# main1.net
KiCad netlist of a schematic drawn in EAGLE
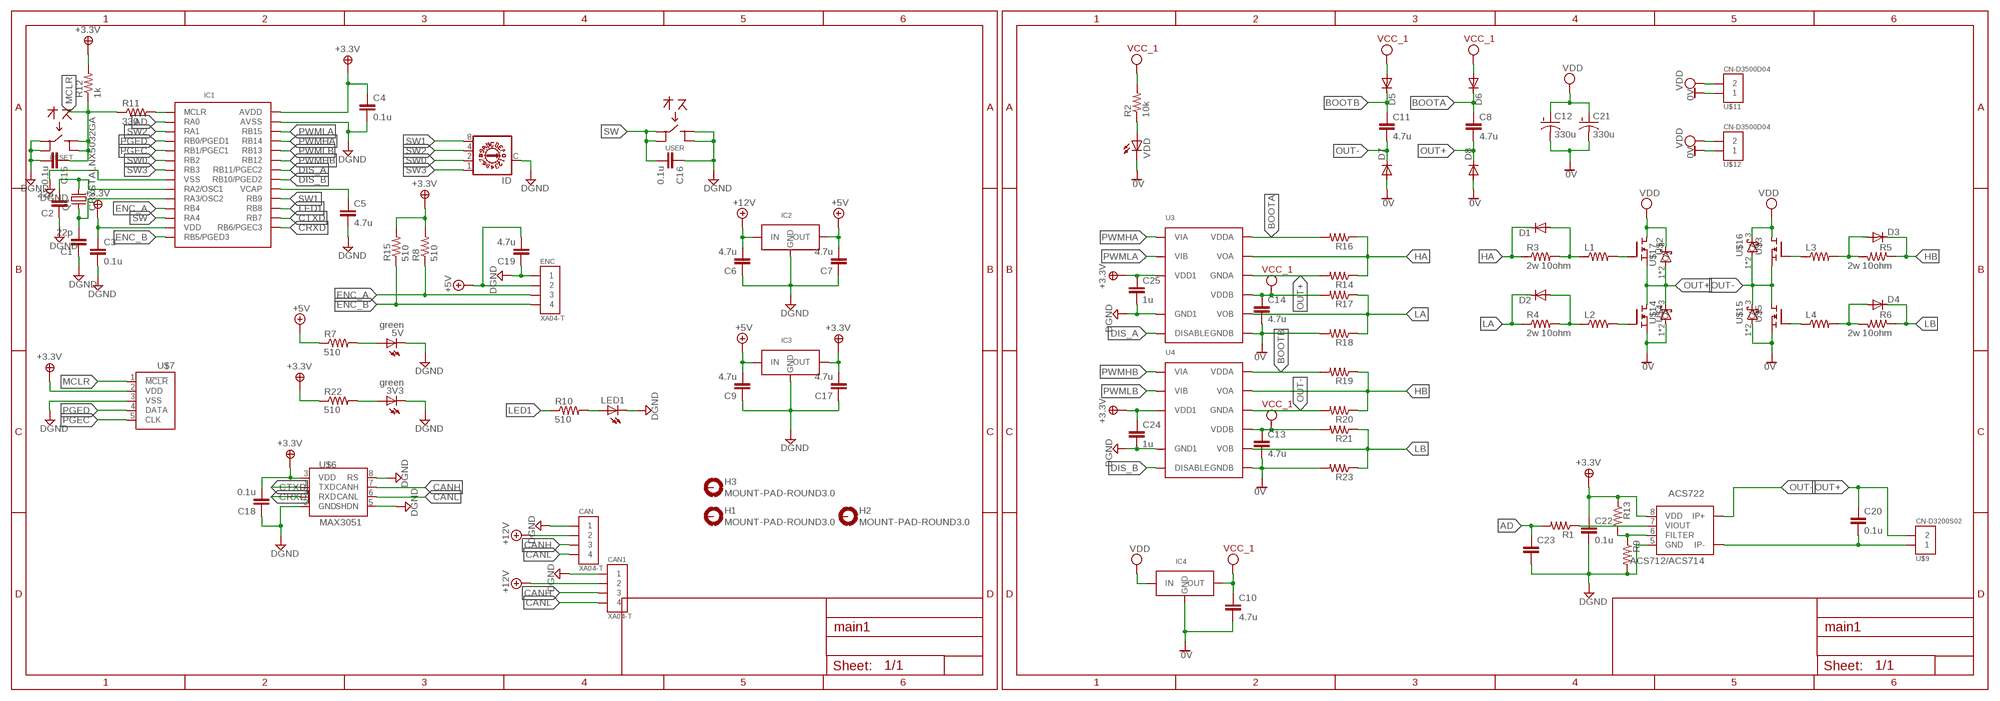
[diagram p0: schematic, sheet 1]

(export (version "E")
  (design (tool "Eeschema 10.0.6"))
  (components
    (comp (ref "3V3")
      (value "green")
      (footprint "eagle-import:CHIPLED_0603")
      (libsource (lib "eagle-import") (part "LEDCHIPLED_0603"))
    )
    (comp (ref "5V")
      (value "green")
      (footprint "eagle-import:CHIPLED_0603")
      (libsource (lib "eagle-import") (part "LEDCHIPLED_0603"))
    )
    (comp (ref "ACS722")
      (value "ACS712/ACS714")
      (footprint "eagle-import:SOIC8")
      (libsource (lib "eagle-import") (part "ACS712/ACS714"))
    )
    (comp (ref "C1")
      (value "22p")
      (footprint "eagle-import:C0603K")
      (libsource (lib "eagle-import") (part "C-EUC0603K"))
    )
    (comp (ref "C2")
      (value "22p")
      (footprint "eagle-import:C0603K")
      (libsource (lib "eagle-import") (part "C-EUC0603K"))
    )
    (comp (ref "C3")
      (value "0.1u")
      (footprint "eagle-import:C0603K")
      (libsource (lib "eagle-import") (part "C-EUC0603K"))
    )
    (comp (ref "C4")
      (value "0.1u")
      (footprint "eagle-import:C0603K")
      (libsource (lib "eagle-import") (part "C-EUC0603K"))
    )
    (comp (ref "C5")
      (value "4.7u")
      (footprint "eagle-import:C0805K")
      (libsource (lib "eagle-import") (part "C-EUC0805K"))
    )
    (comp (ref "C6")
      (value "4.7u")
      (footprint "eagle-import:C0805K")
      (libsource (lib "eagle-import") (part "C-EUC0805K"))
    )
    (comp (ref "C7")
      (value "4.7u")
      (footprint "eagle-import:C0805K")
      (libsource (lib "eagle-import") (part "C-EUC0805K"))
    )
    (comp (ref "C8")
      (value "4.7u")
      (footprint "eagle-import:C0805K")
      (libsource (lib "eagle-import") (part "C-EUC0805K"))
    )
    (comp (ref "C9")
      (value "4.7u")
      (footprint "eagle-import:C0805K")
      (libsource (lib "eagle-import") (part "C-EUC0805K"))
    )
    (comp (ref "C10")
      (value "4.7u")
      (footprint "eagle-import:C0805K")
      (libsource (lib "eagle-import") (part "C-EUC0805K"))
    )
    (comp (ref "C11")
      (value "4.7u")
      (footprint "eagle-import:C0805K")
      (libsource (lib "eagle-import") (part "C-EUC0805K"))
    )
    (comp (ref "C12")
      (value "330u")
      (footprint "eagle-import:PANASONIC_G")
      (libsource (lib "eagle-import") (part "CPOL-USG"))
    )
    (comp (ref "C13")
      (value "4.7u")
      (footprint "eagle-import:C0805K")
      (libsource (lib "eagle-import") (part "C-EUC0805K"))
    )
    (comp (ref "C14")
      (value "4.7u")
      (footprint "eagle-import:C0805K")
      (libsource (lib "eagle-import") (part "C-EUC0805K"))
    )
    (comp (ref "C15")
      (value "0.1u")
      (footprint "eagle-import:C0603K")
      (libsource (lib "eagle-import") (part "C-EUC0603K"))
    )
    (comp (ref "C16")
      (value "0.1u")
      (footprint "eagle-import:C0603K")
      (libsource (lib "eagle-import") (part "C-EUC0603K"))
    )
    (comp (ref "C17")
      (value "4.7u")
      (footprint "eagle-import:C0805K")
      (libsource (lib "eagle-import") (part "C-EUC0805K"))
    )
    (comp (ref "C18")
      (value "0.1u")
      (footprint "eagle-import:C0603K")
      (libsource (lib "eagle-import") (part "C-EUC0603K"))
    )
    (comp (ref "C19")
      (value "4.7u")
      (footprint "eagle-import:C0805K")
      (libsource (lib "eagle-import") (part "C-EUC0805K"))
    )
    (comp (ref "C20")
      (value "0.1u")
      (footprint "eagle-import:C0603K")
      (libsource (lib "eagle-import") (part "C-EUC0603K"))
    )
    (comp (ref "C21")
      (value "330u")
      (footprint "eagle-import:PANASONIC_G")
      (libsource (lib "eagle-import") (part "CPOL-USG"))
    )
    (comp (ref "C22")
      (value "0.1u")
      (footprint "eagle-import:C1206")
      (libsource (lib "eagle-import") (part "C-EUC1206"))
    )
    (comp (ref "C23")
      (value "C-EUC0603K")
      (footprint "eagle-import:C0603K")
      (libsource (lib "eagle-import") (part "C-EUC0603K"))
    )
    (comp (ref "C24")
      (value "1u")
      (footprint "eagle-import:C0603K")
      (libsource (lib "eagle-import") (part "C-EUC0603K"))
    )
    (comp (ref "C25")
      (value "1u")
      (footprint "eagle-import:C0603K")
      (libsource (lib "eagle-import") (part "C-EUC0603K"))
    )
    (comp (ref "CAN")
      (value "XA04-T")
      (footprint "eagle-import:XA04")
      (libsource (lib "eagle-import") (part "XA04-T"))
    )
    (comp (ref "CAN1")
      (value "XA04-T")
      (footprint "eagle-import:XA04")
      (libsource (lib "eagle-import") (part "XA04-T"))
    )
    (comp (ref "D1")
      (value "DIODE-SOD123")
      (footprint "eagle-import:SOD123")
      (libsource (lib "eagle-import") (part "DIODE-SOD123"))
    )
    (comp (ref "D2")
      (value "DIODE-SOD123")
      (footprint "eagle-import:SOD123")
      (libsource (lib "eagle-import") (part "DIODE-SOD123"))
    )
    (comp (ref "D3")
      (value "DIODE-SOD123")
      (footprint "eagle-import:SOD123")
      (libsource (lib "eagle-import") (part "DIODE-SOD123"))
    )
    (comp (ref "D4")
      (value "DIODE-SOD123")
      (footprint "eagle-import:SOD123")
      (libsource (lib "eagle-import") (part "DIODE-SOD123"))
    )
    (comp (ref "D5")
      (value "DIODE-SOD123")
      (footprint "eagle-import:SOD123")
      (libsource (lib "eagle-import") (part "DIODE-SOD123"))
    )
    (comp (ref "D6")
      (value "DIODE-SOD123")
      (footprint "eagle-import:SOD123")
      (libsource (lib "eagle-import") (part "DIODE-SOD123"))
    )
    (comp (ref "D7")
      (value "DIODE-SOD123")
      (footprint "eagle-import:SOD123")
      (libsource (lib "eagle-import") (part "DIODE-SOD123"))
    )
    (comp (ref "D8")
      (value "DIODE-SOD123")
      (footprint "eagle-import:SOD123")
      (libsource (lib "eagle-import") (part "DIODE-SOD123"))
    )
    (comp (ref "ENC")
      (value "XA04-T")
      (footprint "eagle-import:XA04")
      (libsource (lib "eagle-import") (part "XA04-T"))
    )
    (comp (ref "H1")
      (value "MOUNT-PAD-ROUND3.0")
      (footprint "eagle-import:3,0-PAD")
      (libsource (lib "eagle-import") (part "MOUNT-PAD-ROUND3.0"))
    )
    (comp (ref "H2")
      (value "MOUNT-PAD-ROUND3.0")
      (footprint "eagle-import:3,0-PAD")
      (libsource (lib "eagle-import") (part "MOUNT-PAD-ROUND3.0"))
    )
    (comp (ref "H3")
      (value "MOUNT-PAD-ROUND3.0")
      (footprint "eagle-import:3,0-PAD")
      (libsource (lib "eagle-import") (part "MOUNT-PAD-ROUND3.0"))
    )
    (comp (ref "IC1")
      (value "DSPIC33FJ128MC802")
      (footprint "eagle-import:SOIC28")
      (libsource (lib "eagle-import") (part "DSPIC33FJ128MC802"))
    )
    (comp (ref "IC2")
      (value "REGULATER_MIC39100-5.0WS")
      (footprint "eagle-import:SOT-223")
      (libsource (lib "eagle-import") (part "REGULATER_MIC39100-3.3WS"))
    )
    (comp (ref "IC3")
      (value "REGULATER_AZ1117CR")
      (footprint "eagle-import:SOT89")
      (libsource (lib "eagle-import") (part "REGULATER_AZ1117CR"))
    )
    (comp (ref "IC4")
      (value "REGULATER_MIC2940A-5.0WU")
      (footprint "eagle-import:TO-263-3")
      (libsource (lib "eagle-import") (part "REGULATER_MIC2940A-5.0WU"))
    )
    (comp (ref "ID")
      (value "A1353HEX")
      (footprint "eagle-import:A1353HEX")
      (libsource (lib "eagle-import") (part "A1353HEX"))
    )
    (comp (ref "L1")
      (value "R-US_R0805")
      (footprint "eagle-import:R0805")
      (libsource (lib "eagle-import") (part "R-US_R0805"))
    )
    (comp (ref "L2")
      (value "R-US_R0805")
      (footprint "eagle-import:R0805")
      (libsource (lib "eagle-import") (part "R-US_R0805"))
    )
    (comp (ref "L3")
      (value "R-US_R0805")
      (footprint "eagle-import:R0805")
      (libsource (lib "eagle-import") (part "R-US_R0805"))
    )
    (comp (ref "L4")
      (value "R-US_R0805")
      (footprint "eagle-import:R0805")
      (libsource (lib "eagle-import") (part "R-US_R0805"))
    )
    (comp (ref "LED1")
      (value "LEDCHIPLED_0603")
      (footprint "eagle-import:CHIPLED_0603")
      (libsource (lib "eagle-import") (part "LEDCHIPLED_0603"))
    )
    (comp (ref "Q1")
      (value "CRYSTALNX5032GA")
      (footprint "eagle-import:NX5032GA")
      (libsource (lib "eagle-import") (part "CRYSTALNX5032GA"))
    )
    (comp (ref "R1")
      (value "R-US_R0603")
      (footprint "eagle-import:R0603")
      (libsource (lib "eagle-import") (part "R-US_R0603"))
    )
    (comp (ref "R2")
      (value "10k")
      (footprint "eagle-import:R0603")
      (libsource (lib "eagle-import") (part "R-US_R0603"))
    )
    (comp (ref "R3")
      (value "2w 10ohm")
      (footprint "eagle-import:R2512")
      (libsource (lib "eagle-import") (part "R-US_R2512"))
    )
    (comp (ref "R4")
      (value "2w 10ohm")
      (footprint "eagle-import:R2512")
      (libsource (lib "eagle-import") (part "R-US_R2512"))
    )
    (comp (ref "R5")
      (value "2w 10ohm")
      (footprint "eagle-import:R2512")
      (libsource (lib "eagle-import") (part "R-US_R2512"))
    )
    (comp (ref "R6")
      (value "2w 10ohm")
      (footprint "eagle-import:R2512")
      (libsource (lib "eagle-import") (part "R-US_R2512"))
    )
    (comp (ref "R7")
      (value "510")
      (footprint "eagle-import:R0603")
      (libsource (lib "eagle-import") (part "R-US_R0603"))
    )
    (comp (ref "R8")
      (value "510")
      (footprint "eagle-import:R0603")
      (libsource (lib "eagle-import") (part "R-US_R0603"))
    )
    (comp (ref "R9")
      (value "R-US_R0603")
      (footprint "eagle-import:R0603")
      (libsource (lib "eagle-import") (part "R-US_R0603"))
    )
    (comp (ref "R10")
      (value "510")
      (footprint "eagle-import:R0603")
      (libsource (lib "eagle-import") (part "R-US_R0603"))
    )
    (comp (ref "R11")
      (value "330")
      (footprint "eagle-import:R0603")
      (libsource (lib "eagle-import") (part "R-US_R0603"))
    )
    (comp (ref "R12")
      (value "1k")
      (footprint "eagle-import:R0603")
      (libsource (lib "eagle-import") (part "R-US_R0603"))
    )
    (comp (ref "R13")
      (value "R-US_R0603")
      (footprint "eagle-import:R0603")
      (libsource (lib "eagle-import") (part "R-US_R0603"))
    )
    (comp (ref "R14")
      (value "R-US_R0603")
      (footprint "eagle-import:R0603")
      (libsource (lib "eagle-import") (part "R-US_R0603"))
    )
    (comp (ref "R15")
      (value "510")
      (footprint "eagle-import:R0603")
      (libsource (lib "eagle-import") (part "R-US_R0603"))
    )
    (comp (ref "R16")
      (value "R-US_R0603")
      (footprint "eagle-import:R0603")
      (libsource (lib "eagle-import") (part "R-US_R0603"))
    )
    (comp (ref "R17")
      (value "R-US_R0603")
      (footprint "eagle-import:R0603")
      (libsource (lib "eagle-import") (part "R-US_R0603"))
    )
    (comp (ref "R18")
      (value "R-US_R0603")
      (footprint "eagle-import:R0603")
      (libsource (lib "eagle-import") (part "R-US_R0603"))
    )
    (comp (ref "R19")
      (value "R-US_R0603")
      (footprint "eagle-import:R0603")
      (libsource (lib "eagle-import") (part "R-US_R0603"))
    )
    (comp (ref "R20")
      (value "R-US_R0603")
      (footprint "eagle-import:R0603")
      (libsource (lib "eagle-import") (part "R-US_R0603"))
    )
    (comp (ref "R21")
      (value "R-US_R0603")
      (footprint "eagle-import:R0603")
      (libsource (lib "eagle-import") (part "R-US_R0603"))
    )
    (comp (ref "R22")
      (value "510")
      (footprint "eagle-import:R0603")
      (libsource (lib "eagle-import") (part "R-US_R0603"))
    )
    (comp (ref "R23")
      (value "R-US_R0603")
      (footprint "eagle-import:R0603")
      (libsource (lib "eagle-import") (part "R-US_R0603"))
    )
    (comp (ref "RESET")
      (value "SWITCH_4PALPS")
      (footprint "eagle-import:SKRP")
      (libsource (lib "eagle-import") (part "SWITCH_4PALPS"))
    )
    (comp (ref "U$1")
      (value "CN-D3500D04")
      (footprint "eagle-import:D-3500D04")
      (libsource (lib "eagle-import") (part "CN-D3500D04"))
    )
    (comp (ref "U$2")
      (value "FET_NCH_FDMS86152")
      (footprint "eagle-import:PQFN_8L")
      (libsource (lib "eagle-import") (part "FET_NCH_FDMS86152"))
    )
    (comp (ref "U$3")
      (value "FET_NCH_FDMS86152")
      (footprint "eagle-import:PQFN_8L")
      (libsource (lib "eagle-import") (part "FET_NCH_FDMS86152"))
    )
    (comp (ref "U$4")
      (value "FET_NCH_FDMS86152")
      (footprint "eagle-import:PQFN_8L")
      (libsource (lib "eagle-import") (part "FET_NCH_FDMS86152"))
    )
    (comp (ref "U$5")
      (value "FET_NCH_FDMS86152")
      (footprint "eagle-import:PQFN_8L")
      (libsource (lib "eagle-import") (part "FET_NCH_FDMS86152"))
    )
    (comp (ref "U$6")
      (value "MAX3051")
      (footprint "eagle-import:SOIC8")
      (libsource (lib "eagle-import") (part "MAX3051"))
    )
    (comp (ref "U$7")
      (value "WRITE_FOR_PICT")
      (footprint "eagle-import:ZH05")
      (libsource (lib "eagle-import") (part "WRITE_FOR_PICT"))
    )
    (comp (ref "U$9")
      (value "CN-D3200S02")
      (footprint "eagle-import:D-3200S02-S")
      (libsource (lib "eagle-import") (part "CN-D3200S02"))
    )
    (comp (ref "U$14")
      (value "SCHOTTKY_BARRIER_DIODE_FSV560")
      (footprint "eagle-import:TO-277")
      (libsource (lib "eagle-import") (part "SCHOTTKY_BARRIER_DIODE_FSV560"))
    )
    (comp (ref "U$15")
      (value "SCHOTTKY_BARRIER_DIODE_FSV560")
      (footprint "eagle-import:TO-277")
      (libsource (lib "eagle-import") (part "SCHOTTKY_BARRIER_DIODE_FSV560"))
    )
    (comp (ref "U$16")
      (value "SCHOTTKY_BARRIER_DIODE_FSV560")
      (footprint "eagle-import:TO-277")
      (libsource (lib "eagle-import") (part "SCHOTTKY_BARRIER_DIODE_FSV560"))
    )
    (comp (ref "U$17")
      (value "SCHOTTKY_BARRIER_DIODE_FSV560")
      (footprint "eagle-import:TO-277")
      (libsource (lib "eagle-import") (part "SCHOTTKY_BARRIER_DIODE_FSV560"))
    )
    (comp (ref "U3")
      (value "ADUM3223_SMD")
      (footprint "eagle-import:SOIC16_N")
      (libsource (lib "eagle-import") (part "ADUM3223_SMD"))
    )
    (comp (ref "U4")
      (value "ADUM3223_SMD")
      (footprint "eagle-import:SOIC16_N")
      (libsource (lib "eagle-import") (part "ADUM3223_SMD"))
    )
    (comp (ref "USER")
      (value "SWITCH_4PALPS")
      (footprint "eagle-import:SKRP")
      (libsource (lib "eagle-import") (part "SWITCH_4PALPS"))
    )
    (comp (ref "VDD")
      (value "LEDCHIPLED_0603")
      (footprint "eagle-import:CHIPLED_0603")
      (libsource (lib "eagle-import") (part "LEDCHIPLED_0603"))
    )
  )
  (nets
    (net (code "1") (name "+3.3V") (class "Default")
      (node (ref "ACS722") (pin "8") (pinfunction "VDD_8") (pintype "bidirectional"))
      (node (ref "C17") (pin "2") (pinfunction "2_2") (pintype "passive"))
      (node (ref "C18") (pin "2") (pinfunction "2_2") (pintype "passive"))
      (node (ref "C22") (pin "1") (pinfunction "1_1") (pintype "passive"))
      (node (ref "C24") (pin "1") (pinfunction "1_1") (pintype "passive"))
      (node (ref "C25") (pin "1") (pinfunction "1_1") (pintype "passive"))
      (node (ref "C3") (pin "1") (pinfunction "1_1") (pintype "passive"))
      (node (ref "C4") (pin "1") (pinfunction "1_1") (pintype "passive"))
      (node (ref "IC1") (pin "13") (pinfunction "VDD_13") (pintype "bidirectional"))
      (node (ref "IC1") (pin "28") (pinfunction "AVDD_28") (pintype "bidirectional"))
      (node (ref "IC3") (pin "2") (pinfunction "OUT_2") (pintype "bidirectional"))
      (node (ref "IC3") (pin "P") (pinfunction "OUT_P") (pintype "bidirectional"))
      (node (ref "R12") (pin "2") (pinfunction "2_2") (pintype "passive"))
      (node (ref "R13") (pin "1") (pinfunction "1_1") (pintype "passive"))
      (node (ref "R15") (pin "2") (pinfunction "2_2") (pintype "passive"))
      (node (ref "R22") (pin "1") (pinfunction "1_1") (pintype "passive"))
      (node (ref "R8") (pin "2") (pinfunction "2_2") (pintype "passive"))
      (node (ref "U$6") (pin "3") (pinfunction "VDD_3") (pintype "bidirectional"))
      (node (ref "U$7") (pin "2") (pinfunction "VDD_2") (pintype "bidirectional"))
      (node (ref "U3") (pin "P$3") (pinfunction "VDD1_P$3") (pintype "bidirectional"))
      (node (ref "U3") (pin "P$8") (pinfunction "VDD1_P$8") (pintype "bidirectional"))
      (node (ref "U4") (pin "P$3") (pinfunction "VDD1_P$3") (pintype "bidirectional"))
      (node (ref "U4") (pin "P$8") (pinfunction "VDD1_P$8") (pintype "bidirectional"))
    )
    (net (code "2") (name "+5V") (class "Default")
      (node (ref "C19") (pin "2") (pinfunction "2_2") (pintype "passive"))
      (node (ref "C7") (pin "2") (pinfunction "2_2") (pintype "passive"))
      (node (ref "C9") (pin "2") (pinfunction "2_2") (pintype "passive"))
      (node (ref "ENC") (pin "PIN2") (pinfunction "2_PIN2") (pintype "bidirectional"))
      (node (ref "IC2") (pin "3") (pinfunction "OUT_3") (pintype "bidirectional"))
      (node (ref "IC3") (pin "3") (pinfunction "IN_3") (pintype "bidirectional"))
      (node (ref "R7") (pin "1") (pinfunction "1_1") (pintype "passive"))
    )
    (net (code "3") (name "+12V") (class "Default")
      (node (ref "C6") (pin "2") (pinfunction "2_2") (pintype "passive"))
      (node (ref "CAN") (pin "PIN2") (pinfunction "2_PIN2") (pintype "bidirectional"))
      (node (ref "CAN1") (pin "PIN2") (pinfunction "2_PIN2") (pintype "bidirectional"))
      (node (ref "IC2") (pin "1") (pinfunction "IN_1") (pintype "bidirectional"))
    )
    (net (code "4") (name "0V") (class "Default")
      (node (ref "C10") (pin "2") (pinfunction "2_2") (pintype "passive"))
      (node (ref "C12") (pin "-") (pinfunction "-_-") (pintype "passive"))
      (node (ref "C13") (pin "2") (pinfunction "2_2") (pintype "passive"))
      (node (ref "C14") (pin "2") (pinfunction "2_2") (pintype "passive"))
      (node (ref "C21") (pin "-") (pinfunction "-_-") (pintype "passive"))
      (node (ref "D7") (pin "A") (pinfunction "A_A") (pintype "passive"))
      (node (ref "D8") (pin "A") (pinfunction "A_A") (pintype "passive"))
      (node (ref "IC4") (pin "2") (pinfunction "GND_2") (pintype "bidirectional"))
      (node (ref "IC4") (pin "PAD") (pinfunction "GND_PAD") (pintype "bidirectional"))
      (node (ref "R18") (pin "2") (pinfunction "2_2") (pintype "passive"))
      (node (ref "R23") (pin "2") (pinfunction "2_2") (pintype "passive"))
      (node (ref "U$1") (pin "01A") (pinfunction "1_01A") (pintype "bidirectional"))
      (node (ref "U$1") (pin "02A") (pinfunction "1_02A") (pintype "bidirectional"))
      (node (ref "U$14") (pin "1") (pinfunction "A_1") (pintype "bidirectional"))
      (node (ref "U$14") (pin "2") (pinfunction "A_2") (pintype "bidirectional"))
      (node (ref "U$15") (pin "1") (pinfunction "A_1") (pintype "bidirectional"))
      (node (ref "U$15") (pin "2") (pinfunction "A_2") (pintype "bidirectional"))
      (node (ref "U$4") (pin "1") (pinfunction "S_1") (pintype "bidirectional"))
      (node (ref "U$4") (pin "2") (pinfunction "S_2") (pintype "bidirectional"))
      (node (ref "U$4") (pin "3") (pinfunction "S_3") (pintype "bidirectional"))
      (node (ref "U$5") (pin "1") (pinfunction "S_1") (pintype "bidirectional"))
      (node (ref "U$5") (pin "2") (pinfunction "S_2") (pintype "bidirectional"))
      (node (ref "U$5") (pin "3") (pinfunction "S_3") (pintype "bidirectional"))
      (node (ref "U3") (pin "P$9") (pinfunction "GNDB_P$9") (pintype "bidirectional"))
      (node (ref "U4") (pin "P$9") (pinfunction "GNDB_P$9") (pintype "bidirectional"))
      (node (ref "VDD") (pin "C") (pinfunction "C_C") (pintype "passive"))
    )
    (net (code "5") (name "AD") (class "Default")
      (node (ref "C23") (pin "1") (pinfunction "1_1") (pintype "passive"))
      (node (ref "IC1") (pin "2") (pinfunction "RA0_2") (pintype "bidirectional"))
      (node (ref "R1") (pin "2") (pinfunction "2_2") (pintype "passive"))
    )
    (net (code "6") (name "BOOTA") (class "Default")
      (node (ref "C8") (pin "1") (pinfunction "1_1") (pintype "passive"))
      (node (ref "D6") (pin "C") (pinfunction "C_C") (pintype "passive"))
      (node (ref "R16") (pin "2") (pinfunction "2_2") (pintype "passive"))
      (node (ref "U3") (pin "P$16") (pinfunction "VDDA_P$16") (pintype "bidirectional"))
    )
    (net (code "7") (name "BOOTB") (class "Default")
      (node (ref "C11") (pin "1") (pinfunction "1_1") (pintype "passive"))
      (node (ref "D5") (pin "C") (pinfunction "C_C") (pintype "passive"))
      (node (ref "R19") (pin "2") (pinfunction "2_2") (pintype "passive"))
      (node (ref "U4") (pin "P$16") (pinfunction "VDDA_P$16") (pintype "bidirectional"))
    )
    (net (code "8") (name "CANH") (class "Default")
      (node (ref "CAN") (pin "PIN3") (pinfunction "3_PIN3") (pintype "bidirectional"))
      (node (ref "CAN1") (pin "PIN3") (pinfunction "3_PIN3") (pintype "bidirectional"))
      (node (ref "U$6") (pin "7") (pinfunction "CANH_7") (pintype "bidirectional"))
    )
    (net (code "9") (name "CANL") (class "Default")
      (node (ref "CAN") (pin "PIN4") (pinfunction "4_PIN4") (pintype "bidirectional"))
      (node (ref "CAN1") (pin "PIN4") (pinfunction "4_PIN4") (pintype "bidirectional"))
      (node (ref "U$6") (pin "6") (pinfunction "CANL_6") (pintype "bidirectional"))
    )
    (net (code "10") (name "CRXD") (class "Default")
      (node (ref "IC1") (pin "15") (pinfunction "RB6/PGEC3_15") (pintype "bidirectional"))
      (node (ref "U$6") (pin "4") (pinfunction "RXD_4") (pintype "bidirectional"))
    )
    (net (code "11") (name "CTXD") (class "Default")
      (node (ref "IC1") (pin "16") (pinfunction "RB7_16") (pintype "bidirectional"))
      (node (ref "U$6") (pin "1") (pinfunction "TXD_1") (pintype "bidirectional"))
    )
    (net (code "12") (name "DGND") (class "Default")
      (node (ref "3V3") (pin "C") (pinfunction "C_C") (pintype "passive"))
      (node (ref "5V") (pin "C") (pinfunction "C_C") (pintype "passive"))
      (node (ref "ACS722") (pin "5") (pinfunction "GND_5") (pintype "bidirectional"))
      (node (ref "C1") (pin "1") (pinfunction "1_1") (pintype "passive"))
      (node (ref "C15") (pin "2") (pinfunction "2_2") (pintype "passive"))
      (node (ref "C16") (pin "1") (pinfunction "1_1") (pintype "passive"))
      (node (ref "C17") (pin "1") (pinfunction "1_1") (pintype "passive"))
      (node (ref "C18") (pin "1") (pinfunction "1_1") (pintype "passive"))
      (node (ref "C19") (pin "1") (pinfunction "1_1") (pintype "passive"))
      (node (ref "C2") (pin "1") (pinfunction "1_1") (pintype "passive"))
      (node (ref "C22") (pin "2") (pinfunction "2_2") (pintype "passive"))
      (node (ref "C23") (pin "2") (pinfunction "2_2") (pintype "passive"))
      (node (ref "C24") (pin "2") (pinfunction "2_2") (pintype "passive"))
      (node (ref "C25") (pin "2") (pinfunction "2_2") (pintype "passive"))
      (node (ref "C3") (pin "2") (pinfunction "2_2") (pintype "passive"))
      (node (ref "C4") (pin "2") (pinfunction "2_2") (pintype "passive"))
      (node (ref "C5") (pin "2") (pinfunction "2_2") (pintype "passive"))
      (node (ref "C6") (pin "1") (pinfunction "1_1") (pintype "passive"))
      (node (ref "C7") (pin "1") (pinfunction "1_1") (pintype "passive"))
      (node (ref "C9") (pin "1") (pinfunction "1_1") (pintype "passive"))
      (node (ref "CAN") (pin "PIN1") (pinfunction "1_PIN1") (pintype "bidirectional"))
      (node (ref "CAN1") (pin "PIN1") (pinfunction "1_PIN1") (pintype "bidirectional"))
      (node (ref "ENC") (pin "PIN1") (pinfunction "1_PIN1") (pintype "bidirectional"))
      (node (ref "IC1") (pin "19") (pinfunction "VSS_19") (pintype "bidirectional"))
      (node (ref "IC1") (pin "27") (pinfunction "AVSS_27") (pintype "bidirectional"))
      (node (ref "IC1") (pin "8") (pinfunction "VSS_8") (pintype "bidirectional"))
      (node (ref "IC2") (pin "2") (pinfunction "GND_2") (pintype "bidirectional"))
      (node (ref "IC2") (pin "TAB") (pinfunction "GND_TAB") (pintype "bidirectional"))
      (node (ref "IC3") (pin "1") (pinfunction "GND_1") (pintype "bidirectional"))
      (node (ref "ID") (pin "C") (pinfunction "C_C") (pintype "passive"))
      (node (ref "LED1") (pin "C") (pinfunction "C_C") (pintype "passive"))
      (node (ref "R9") (pin "2") (pinfunction "2_2") (pintype "passive"))
      (node (ref "RESET") (pin "1") (pinfunction "1_1") (pintype "bidirectional"))
      (node (ref "RESET") (pin "2") (pinfunction "2_2") (pintype "bidirectional"))
      (node (ref "U$6") (pin "2") (pinfunction "GND_2") (pintype "bidirectional"))
      (node (ref "U$6") (pin "5") (pinfunction "SHDN_5") (pintype "bidirectional"))
      (node (ref "U$6") (pin "8") (pinfunction "RS_8") (pintype "bidirectional"))
      (node (ref "U$7") (pin "3") (pinfunction "VSS_3") (pintype "bidirectional"))
      (node (ref "U3") (pin "P$4") (pinfunction "GND1_P$4") (pintype "bidirectional"))
      (node (ref "U4") (pin "P$4") (pinfunction "GND1_P$4") (pintype "bidirectional"))
      (node (ref "USER") (pin "3") (pinfunction "3_3") (pintype "bidirectional"))
      (node (ref "USER") (pin "4") (pinfunction "4_4") (pintype "bidirectional"))
    )
    (net (code "13") (name "DIS_A") (class "Default")
      (node (ref "IC1") (pin "22") (pinfunction "RB11/PGEC2_22") (pintype "bidirectional"))
      (node (ref "U3") (pin "P$5") (pinfunction "DISABLE_P$5") (pintype "bidirectional"))
    )
    (net (code "14") (name "DIS_B") (class "Default")
      (node (ref "IC1") (pin "21") (pinfunction "RB10/PGED2_21") (pintype "bidirectional"))
      (node (ref "U4") (pin "P$5") (pinfunction "DISABLE_P$5") (pintype "bidirectional"))
    )
    (net (code "15") (name "ENC_A") (class "Default")
      (node (ref "ENC") (pin "PIN3") (pinfunction "3_PIN3") (pintype "bidirectional"))
      (node (ref "IC1") (pin "11") (pinfunction "RB4_11") (pintype "bidirectional"))
      (node (ref "R8") (pin "1") (pinfunction "1_1") (pintype "passive"))
    )
    (net (code "16") (name "ENC_B") (class "Default")
      (node (ref "ENC") (pin "PIN4") (pinfunction "4_PIN4") (pintype "bidirectional"))
      (node (ref "IC1") (pin "14") (pinfunction "RB5/PGED3_14") (pintype "bidirectional"))
      (node (ref "R15") (pin "1") (pinfunction "1_1") (pintype "passive"))
    )
    (net (code "17") (name "HA") (class "Default")
      (node (ref "D1") (pin "C") (pinfunction "C_C") (pintype "passive"))
      (node (ref "R14") (pin "1") (pinfunction "1_1") (pintype "passive"))
      (node (ref "R16") (pin "1") (pinfunction "1_1") (pintype "passive"))
      (node (ref "R3") (pin "1") (pinfunction "1_1") (pintype "passive"))
      (node (ref "U3") (pin "P$15") (pinfunction "VOA_P$15") (pintype "bidirectional"))
    )
    (net (code "18") (name "HB") (class "Default")
      (node (ref "D3") (pin "C") (pinfunction "C_C") (pintype "passive"))
      (node (ref "R19") (pin "1") (pinfunction "1_1") (pintype "passive"))
      (node (ref "R20") (pin "1") (pinfunction "1_1") (pintype "passive"))
      (node (ref "R5") (pin "1") (pinfunction "1_1") (pintype "passive"))
      (node (ref "U4") (pin "P$15") (pinfunction "VOA_P$15") (pintype "bidirectional"))
    )
    (net (code "19") (name "LA") (class "Default")
      (node (ref "D2") (pin "C") (pinfunction "C_C") (pintype "passive"))
      (node (ref "R17") (pin "1") (pinfunction "1_1") (pintype "passive"))
      (node (ref "R18") (pin "1") (pinfunction "1_1") (pintype "passive"))
      (node (ref "R4") (pin "1") (pinfunction "1_1") (pintype "passive"))
      (node (ref "U3") (pin "P$10") (pinfunction "VOB_P$10") (pintype "bidirectional"))
    )
    (net (code "20") (name "LB") (class "Default")
      (node (ref "D4") (pin "C") (pinfunction "C_C") (pintype "passive"))
      (node (ref "R21") (pin "1") (pinfunction "1_1") (pintype "passive"))
      (node (ref "R23") (pin "1") (pinfunction "1_1") (pintype "passive"))
      (node (ref "R6") (pin "1") (pinfunction "1_1") (pintype "passive"))
      (node (ref "U4") (pin "P$10") (pinfunction "VOB_P$10") (pintype "bidirectional"))
    )
    (net (code "21") (name "LED1") (class "Default")
      (node (ref "IC1") (pin "17") (pinfunction "RB8_17") (pintype "bidirectional"))
      (node (ref "R10") (pin "1") (pinfunction "1_1") (pintype "passive"))
    )
    (net (code "22") (name "MCLR") (class "Default")
      (node (ref "C15") (pin "1") (pinfunction "1_1") (pintype "passive"))
      (node (ref "R11") (pin "1") (pinfunction "1_1") (pintype "passive"))
      (node (ref "R12") (pin "1") (pinfunction "1_1") (pintype "passive"))
      (node (ref "RESET") (pin "3") (pinfunction "3_3") (pintype "bidirectional"))
      (node (ref "RESET") (pin "4") (pinfunction "4_4") (pintype "bidirectional"))
      (node (ref "U$7") (pin "1") (pinfunction "~{MCLR}_1") (pintype "bidirectional"))
    )
    (net (code "23") (name "Net-(3V3-PadA)") (class "Default")
      (node (ref "3V3") (pin "A") (pinfunction "A_A") (pintype "passive"))
      (node (ref "R22") (pin "2") (pinfunction "2_2") (pintype "passive"))
    )
    (net (code "24") (name "Net-(5V-PadA)") (class "Default")
      (node (ref "5V") (pin "A") (pinfunction "A_A") (pintype "passive"))
      (node (ref "R7") (pin "2") (pinfunction "2_2") (pintype "passive"))
    )
    (net (code "25") (name "Net-(ACS722-FILTER)") (class "Default")
      (node (ref "ACS722") (pin "6") (pinfunction "FILTER_6") (pintype "bidirectional"))
      (node (ref "R13") (pin "2") (pinfunction "2_2") (pintype "passive"))
      (node (ref "R9") (pin "1") (pinfunction "1_1") (pintype "passive"))
    )
    (net (code "26") (name "Net-(ACS722-IP--Pad3)") (class "Default")
      (node (ref "ACS722") (pin "3") (pinfunction "IP-_3") (pintype "bidirectional"))
      (node (ref "ACS722") (pin "4") (pinfunction "IP-_4") (pintype "bidirectional"))
      (node (ref "C20") (pin "2") (pinfunction "2_2") (pintype "passive"))
      (node (ref "U$9") (pin "1") (pinfunction "1_1") (pintype "bidirectional"))
      (node (ref "U$9") (pin "P$1") (pinfunction "1_P$1") (pintype "bidirectional"))
    )
    (net (code "27") (name "Net-(ACS722-VIOUT)") (class "Default")
      (node (ref "ACS722") (pin "7") (pinfunction "VIOUT_7") (pintype "bidirectional"))
      (node (ref "R1") (pin "1") (pinfunction "1_1") (pintype "passive"))
    )
    (net (code "28") (name "Net-(D1-PadA)") (class "Default")
      (node (ref "D1") (pin "A") (pinfunction "A_A") (pintype "passive"))
      (node (ref "L1") (pin "1") (pinfunction "1_1") (pintype "passive"))
      (node (ref "R3") (pin "2") (pinfunction "2_2") (pintype "passive"))
    )
    (net (code "29") (name "Net-(D2-PadA)") (class "Default")
      (node (ref "D2") (pin "A") (pinfunction "A_A") (pintype "passive"))
      (node (ref "L2") (pin "1") (pinfunction "1_1") (pintype "passive"))
      (node (ref "R4") (pin "2") (pinfunction "2_2") (pintype "passive"))
    )
    (net (code "30") (name "Net-(D3-PadA)") (class "Default")
      (node (ref "D3") (pin "A") (pinfunction "A_A") (pintype "passive"))
      (node (ref "L3") (pin "2") (pinfunction "2_2") (pintype "passive"))
      (node (ref "R5") (pin "2") (pinfunction "2_2") (pintype "passive"))
    )
    (net (code "31") (name "Net-(D4-PadA)") (class "Default")
      (node (ref "D4") (pin "A") (pinfunction "A_A") (pintype "passive"))
      (node (ref "L4") (pin "2") (pinfunction "2_2") (pintype "passive"))
      (node (ref "R6") (pin "2") (pinfunction "2_2") (pintype "passive"))
    )
    (net (code "32") (name "Net-(IC1-MCLR)") (class "Default")
      (node (ref "IC1") (pin "1") (pinfunction "MCLR_1") (pintype "bidirectional"))
      (node (ref "R11") (pin "2") (pinfunction "2_2") (pintype "passive"))
    )
    (net (code "33") (name "Net-(IC1-RA2{slash}OSC1)") (class "Default")
      (node (ref "C2") (pin "2") (pinfunction "2_2") (pintype "passive"))
      (node (ref "IC1") (pin "9") (pinfunction "RA2/OSC1_9") (pintype "bidirectional"))
      (node (ref "Q1") (pin "2") (pinfunction "2_2") (pintype "bidirectional"))
    )
    (net (code "34") (name "Net-(IC1-RA3{slash}OSC2)") (class "Default")
      (node (ref "C1") (pin "2") (pinfunction "2_2") (pintype "passive"))
      (node (ref "IC1") (pin "10") (pinfunction "RA3/OSC2_10") (pintype "bidirectional"))
      (node (ref "Q1") (pin "1") (pinfunction "1_1") (pintype "bidirectional"))
    )
    (net (code "35") (name "Net-(IC1-VCAP)") (class "Default")
      (node (ref "C5") (pin "1") (pinfunction "1_1") (pintype "passive"))
      (node (ref "IC1") (pin "20") (pinfunction "VCAP_20") (pintype "bidirectional"))
    )
    (net (code "36") (name "Net-(LED1-PadA)") (class "Default")
      (node (ref "LED1") (pin "A") (pinfunction "A_A") (pintype "passive"))
      (node (ref "R10") (pin "2") (pinfunction "2_2") (pintype "passive"))
    )
    (net (code "37") (name "Net-(R2-Pad1)") (class "Default")
      (node (ref "R2") (pin "1") (pinfunction "1_1") (pintype "passive"))
      (node (ref "VDD") (pin "A") (pinfunction "A_A") (pintype "passive"))
    )
    (net (code "38") (name "Net-(U$2-G)") (class "Default")
      (node (ref "L1") (pin "2") (pinfunction "2_2") (pintype "passive"))
      (node (ref "U$2") (pin "4") (pinfunction "G_4") (pintype "bidirectional"))
    )
    (net (code "39") (name "Net-(U$3-G)") (class "Default")
      (node (ref "L3") (pin "1") (pinfunction "1_1") (pintype "passive"))
      (node (ref "U$3") (pin "4") (pinfunction "G_4") (pintype "bidirectional"))
    )
    (net (code "40") (name "Net-(U$4-G)") (class "Default")
      (node (ref "L2") (pin "2") (pinfunction "2_2") (pintype "passive"))
      (node (ref "U$4") (pin "4") (pinfunction "G_4") (pintype "bidirectional"))
    )
    (net (code "41") (name "Net-(U$5-G)") (class "Default")
      (node (ref "L4") (pin "1") (pinfunction "1_1") (pintype "passive"))
      (node (ref "U$5") (pin "4") (pinfunction "G_4") (pintype "bidirectional"))
    )
    (net (code "42") (name "OUT+") (class "Default")
      (node (ref "C20") (pin "1") (pinfunction "1_1") (pintype "passive"))
      (node (ref "C8") (pin "2") (pinfunction "2_2") (pintype "passive"))
      (node (ref "D8") (pin "C") (pinfunction "C_C") (pintype "passive"))
      (node (ref "R14") (pin "2") (pinfunction "2_2") (pintype "passive"))
      (node (ref "U$14") (pin "3") (pinfunction "C_3") (pintype "bidirectional"))
      (node (ref "U$17") (pin "1") (pinfunction "A_1") (pintype "bidirectional"))
      (node (ref "U$17") (pin "2") (pinfunction "A_2") (pintype "bidirectional"))
      (node (ref "U$2") (pin "1") (pinfunction "S_1") (pintype "bidirectional"))
      (node (ref "U$2") (pin "2") (pinfunction "S_2") (pintype "bidirectional"))
      (node (ref "U$2") (pin "3") (pinfunction "S_3") (pintype "bidirectional"))
      (node (ref "U$4") (pin "5") (pinfunction "D_5") (pintype "bidirectional"))
      (node (ref "U$4") (pin "6") (pinfunction "D_6") (pintype "bidirectional"))
      (node (ref "U$4") (pin "7") (pinfunction "D_7") (pintype "bidirectional"))
      (node (ref "U$4") (pin "8") (pinfunction "D_8") (pintype "bidirectional"))
      (node (ref "U$4") (pin "PAD") (pinfunction "D_PAD") (pintype "bidirectional"))
      (node (ref "U$9") (pin "2") (pinfunction "2_2") (pintype "bidirectional"))
      (node (ref "U$9") (pin "P$2") (pinfunction "2_P$2") (pintype "bidirectional"))
      (node (ref "U3") (pin "P$14") (pinfunction "GNDA_P$14") (pintype "bidirectional"))
    )
    (net (code "43") (name "OUT-") (class "Default")
      (node (ref "ACS722") (pin "1") (pinfunction "IP+_1") (pintype "bidirectional"))
      (node (ref "ACS722") (pin "2") (pinfunction "IP+_2") (pintype "bidirectional"))
      (node (ref "C11") (pin "2") (pinfunction "2_2") (pintype "passive"))
      (node (ref "D7") (pin "C") (pinfunction "C_C") (pintype "passive"))
      (node (ref "R20") (pin "2") (pinfunction "2_2") (pintype "passive"))
      (node (ref "U$15") (pin "3") (pinfunction "C_3") (pintype "bidirectional"))
      (node (ref "U$16") (pin "1") (pinfunction "A_1") (pintype "bidirectional"))
      (node (ref "U$16") (pin "2") (pinfunction "A_2") (pintype "bidirectional"))
      (node (ref "U$3") (pin "1") (pinfunction "S_1") (pintype "bidirectional"))
      (node (ref "U$3") (pin "2") (pinfunction "S_2") (pintype "bidirectional"))
      (node (ref "U$3") (pin "3") (pinfunction "S_3") (pintype "bidirectional"))
      (node (ref "U$5") (pin "5") (pinfunction "D_5") (pintype "bidirectional"))
      (node (ref "U$5") (pin "6") (pinfunction "D_6") (pintype "bidirectional"))
      (node (ref "U$5") (pin "7") (pinfunction "D_7") (pintype "bidirectional"))
      (node (ref "U$5") (pin "8") (pinfunction "D_8") (pintype "bidirectional"))
      (node (ref "U$5") (pin "PAD") (pinfunction "D_PAD") (pintype "bidirectional"))
      (node (ref "U4") (pin "P$14") (pinfunction "GNDA_P$14") (pintype "bidirectional"))
    )
    (net (code "44") (name "PGEC") (class "Default")
      (node (ref "IC1") (pin "5") (pinfunction "RB1/PGEC1_5") (pintype "bidirectional"))
      (node (ref "U$7") (pin "5") (pinfunction "CLK_5") (pintype "bidirectional"))
    )
    (net (code "45") (name "PGED") (class "Default")
      (node (ref "IC1") (pin "4") (pinfunction "RB0/PGED1_4") (pintype "bidirectional"))
      (node (ref "U$7") (pin "4") (pinfunction "DATA_4") (pintype "bidirectional"))
    )
    (net (code "46") (name "PWMHA") (class "Default")
      (node (ref "IC1") (pin "25") (pinfunction "RB14_25") (pintype "bidirectional"))
      (node (ref "U3") (pin "P$1") (pinfunction "VIA_P$1") (pintype "bidirectional"))
    )
    (net (code "47") (name "PWMHB") (class "Default")
      (node (ref "IC1") (pin "23") (pinfunction "RB12_23") (pintype "bidirectional"))
      (node (ref "U4") (pin "P$1") (pinfunction "VIA_P$1") (pintype "bidirectional"))
    )
    (net (code "48") (name "PWMLA") (class "Default")
      (node (ref "IC1") (pin "26") (pinfunction "RB15_26") (pintype "bidirectional"))
      (node (ref "U3") (pin "P$2") (pinfunction "VIB_P$2") (pintype "bidirectional"))
    )
    (net (code "49") (name "PWMLB") (class "Default")
      (node (ref "IC1") (pin "24") (pinfunction "RB13_24") (pintype "bidirectional"))
      (node (ref "U4") (pin "P$2") (pinfunction "VIB_P$2") (pintype "bidirectional"))
    )
    (net (code "50") (name "SW") (class "Default")
      (node (ref "C16") (pin "2") (pinfunction "2_2") (pintype "passive"))
      (node (ref "IC1") (pin "12") (pinfunction "RA4_12") (pintype "bidirectional"))
      (node (ref "USER") (pin "1") (pinfunction "1_1") (pintype "bidirectional"))
      (node (ref "USER") (pin "2") (pinfunction "2_2") (pintype "bidirectional"))
    )
    (net (code "51") (name "SW0") (class "Default")
      (node (ref "IC1") (pin "6") (pinfunction "RB2_6") (pintype "bidirectional"))
      (node (ref "ID") (pin "2") (pinfunction "2_2") (pintype "passive"))
    )
    (net (code "52") (name "SW1") (class "Default")
      (node (ref "IC1") (pin "18") (pinfunction "RB9_18") (pintype "bidirectional"))
      (node (ref "ID") (pin "8") (pinfunction "8_8") (pintype "passive"))
    )
    (net (code "53") (name "SW2") (class "Default")
      (node (ref "IC1") (pin "3") (pinfunction "RA1_3") (pintype "bidirectional"))
      (node (ref "ID") (pin "4") (pinfunction "4_4") (pintype "passive"))
    )
    (net (code "54") (name "SW3") (class "Default")
      (node (ref "IC1") (pin "7") (pinfunction "RB3_7") (pintype "bidirectional"))
      (node (ref "ID") (pin "1") (pinfunction "1_1") (pintype "passive"))
    )
    (net (code "55") (name "VCC_1") (class "Default")
      (node (ref "C10") (pin "1") (pinfunction "1_1") (pintype "passive"))
      (node (ref "C13") (pin "1") (pinfunction "1_1") (pintype "passive"))
      (node (ref "C14") (pin "1") (pinfunction "1_1") (pintype "passive"))
      (node (ref "D5") (pin "A") (pinfunction "A_A") (pintype "passive"))
      (node (ref "D6") (pin "A") (pinfunction "A_A") (pintype "passive"))
      (node (ref "IC4") (pin "3") (pinfunction "OUT_3") (pintype "bidirectional"))
      (node (ref "R17") (pin "2") (pinfunction "2_2") (pintype "passive"))
      (node (ref "R2") (pin "2") (pinfunction "2_2") (pintype "passive"))
      (node (ref "R21") (pin "2") (pinfunction "2_2") (pintype "passive"))
      (node (ref "U3") (pin "P$11") (pinfunction "VDDB_P$11") (pintype "bidirectional"))
      (node (ref "U4") (pin "P$11") (pinfunction "VDDB_P$11") (pintype "bidirectional"))
    )
    (net (code "56") (name "VDD") (class "Default")
      (node (ref "C12") (pin "+") (pinfunction "+_+") (pintype "passive"))
      (node (ref "C21") (pin "+") (pinfunction "+_+") (pintype "passive"))
      (node (ref "IC4") (pin "1") (pinfunction "IN_1") (pintype "bidirectional"))
      (node (ref "U$1") (pin "01B") (pinfunction "2_01B") (pintype "bidirectional"))
      (node (ref "U$1") (pin "02B") (pinfunction "2_02B") (pintype "bidirectional"))
      (node (ref "U$16") (pin "3") (pinfunction "C_3") (pintype "bidirectional"))
      (node (ref "U$17") (pin "3") (pinfunction "C_3") (pintype "bidirectional"))
      (node (ref "U$2") (pin "5") (pinfunction "D_5") (pintype "bidirectional"))
      (node (ref "U$2") (pin "6") (pinfunction "D_6") (pintype "bidirectional"))
      (node (ref "U$2") (pin "7") (pinfunction "D_7") (pintype "bidirectional"))
      (node (ref "U$2") (pin "8") (pinfunction "D_8") (pintype "bidirectional"))
      (node (ref "U$2") (pin "PAD") (pinfunction "D_PAD") (pintype "bidirectional"))
      (node (ref "U$3") (pin "5") (pinfunction "D_5") (pintype "bidirectional"))
      (node (ref "U$3") (pin "6") (pinfunction "D_6") (pintype "bidirectional"))
      (node (ref "U$3") (pin "7") (pinfunction "D_7") (pintype "bidirectional"))
      (node (ref "U$3") (pin "8") (pinfunction "D_8") (pintype "bidirectional"))
      (node (ref "U$3") (pin "PAD") (pinfunction "D_PAD") (pintype "bidirectional"))
    )
    (net (code "57") (name "unconnected-(H1-MOUNT-PadB3,0)") (class "Default")
      (node (ref "H1") (pin "B3,0") (pinfunction "MOUNT_B3,0") (pintype "passive"))
    )
    (net (code "58") (name "unconnected-(H2-MOUNT-PadB3,0)") (class "Default")
      (node (ref "H2") (pin "B3,0") (pinfunction "MOUNT_B3,0") (pintype "passive"))
    )
    (net (code "59") (name "unconnected-(H3-MOUNT-PadB3,0)") (class "Default")
      (node (ref "H3") (pin "B3,0") (pinfunction "MOUNT_B3,0") (pintype "passive"))
    )
  )
)
